# BeagleBone_Blue.net
KiCad netlist of a schematic drawn in EAGLE
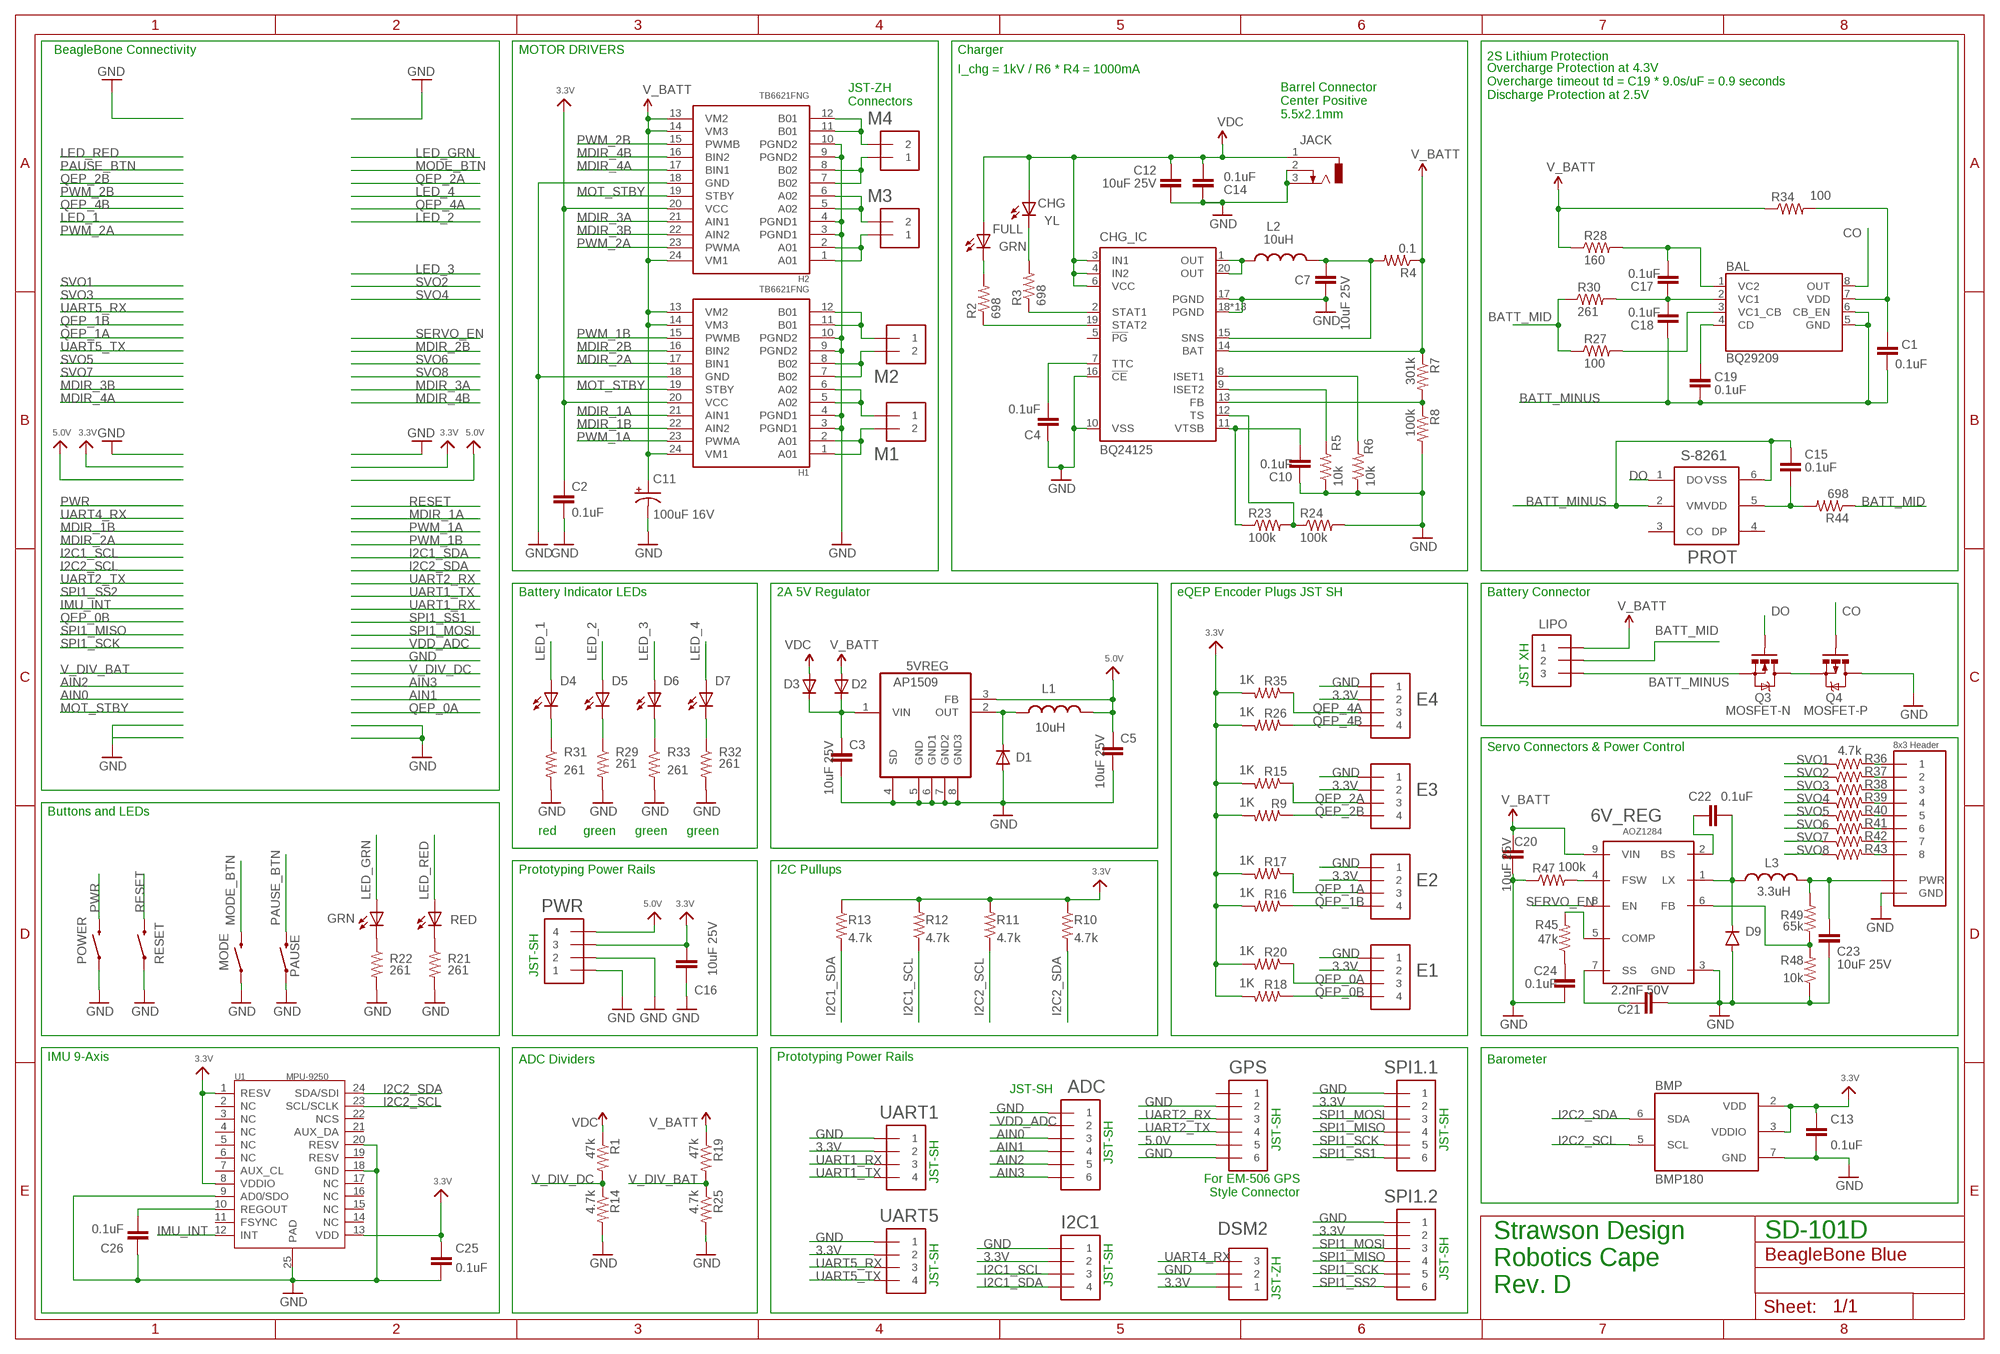
[diagram p0: schematic, sheet 1]

(export (version "E")
  (design (tool "Eeschema 10.0.6"))
  (components
    (comp (ref "5VREG")
      (value "AP1509SOIC-8-TIGHT")
      (footprint "eagle-import:SO08-TIGHT")
      (libsource (lib "eagle-import") (part "AP1509SOIC-8-TIGHT"))
    )
    (comp (ref "6V_REG")
      (value "AOZ1284")
      (footprint "eagle-import:SO08-EXPOSED")
      (libsource (lib "eagle-import") (part "AOZ1284"))
    )
    (comp (ref "ADC")
      (value "JST_SH_6")
      (footprint "eagle-import:JST_SH_6")
      (libsource (lib "eagle-import") (part "JST_SH_6"))
    )
    (comp (ref "BAL")
      (value "BQ29209")
      (footprint "eagle-import:8-SON_3X3MM")
      (libsource (lib "eagle-import") (part "BQ29209"))
    )
    (comp (ref "BMP")
      (value "BMP180")
      (footprint "eagle-import:BMP180")
      (libsource (lib "eagle-import") (part "BMP180"))
    )
    (comp (ref "C1")
      (value "0.1uF")
      (footprint "eagle-import:0402-CAP")
      (libsource (lib "eagle-import") (part "Strawson_Eagle_Lib_CAP0402-CAP"))
    )
    (comp (ref "C2")
      (value "0.1uF")
      (footprint "eagle-import:0402-CAP")
      (libsource (lib "eagle-import") (part "Strawson_Eagle_Lib_CAP0402-CAP"))
    )
    (comp (ref "C3")
      (value "10uF 25V")
      (footprint "eagle-import:0805")
      (libsource (lib "eagle-import") (part "CAP0805"))
    )
    (comp (ref "C4")
      (value "0.1uF")
      (footprint "eagle-import:0402-CAP")
      (libsource (lib "eagle-import") (part "Strawson_Eagle_Lib_CAP0402-CAP"))
    )
    (comp (ref "C5")
      (value "10uF 25V")
      (footprint "eagle-import:0805")
      (libsource (lib "eagle-import") (part "CAP0805"))
    )
    (comp (ref "C7")
      (value "10uF 25V")
      (footprint "eagle-import:0805")
      (libsource (lib "eagle-import") (part "CAP0805"))
    )
    (comp (ref "C10")
      (value "0.1uF")
      (footprint "eagle-import:0402-CAP")
      (libsource (lib "eagle-import") (part "Strawson_Eagle_Lib_CAP0402-CAP"))
    )
    (comp (ref "C11")
      (value "100uF 16V")
      (footprint "eagle-import:PANASONIC_D")
      (libsource (lib "eagle-import") (part "CPOL-USD"))
    )
    (comp (ref "C12")
      (value "10uF 25V")
      (footprint "eagle-import:0805")
      (libsource (lib "eagle-import") (part "CAP0805"))
    )
    (comp (ref "C13")
      (value "0.1uF")
      (footprint "eagle-import:0402-CAP")
      (libsource (lib "eagle-import") (part "Strawson_Eagle_Lib_CAP0402-CAP"))
    )
    (comp (ref "C14")
      (value "0.1uF")
      (footprint "eagle-import:0402-CAP")
      (libsource (lib "eagle-import") (part "Strawson_Eagle_Lib_CAP0402-CAP"))
    )
    (comp (ref "C15")
      (value "0.1uF")
      (footprint "eagle-import:0402-CAP")
      (libsource (lib "eagle-import") (part "Strawson_Eagle_Lib_CAP0402-CAP"))
    )
    (comp (ref "C16")
      (value "10uF 25V")
      (footprint "eagle-import:0805")
      (libsource (lib "eagle-import") (part "CAP0805"))
    )
    (comp (ref "C17")
      (value "0.1uF")
      (footprint "eagle-import:0402-CAP")
      (libsource (lib "eagle-import") (part "Strawson_Eagle_Lib_CAP0402-CAP"))
    )
    (comp (ref "C18")
      (value "0.1uF")
      (footprint "eagle-import:0402-CAP")
      (libsource (lib "eagle-import") (part "Strawson_Eagle_Lib_CAP0402-CAP"))
    )
    (comp (ref "C19")
      (value "0.1uF")
      (footprint "eagle-import:0402-CAP")
      (libsource (lib "eagle-import") (part "Strawson_Eagle_Lib_CAP0402-CAP"))
    )
    (comp (ref "C20")
      (value "10uF 25V")
      (footprint "eagle-import:0805")
      (libsource (lib "eagle-import") (part "CAP0805"))
    )
    (comp (ref "C21")
      (value "2.2nF 50V")
      (footprint "eagle-import:0402-CAP")
      (libsource (lib "eagle-import") (part "Strawson_Eagle_Lib_CAP0402-CAP"))
    )
    (comp (ref "C22")
      (value "0.1uF")
      (footprint "eagle-import:0402-CAP")
      (libsource (lib "eagle-import") (part "Strawson_Eagle_Lib_CAP0402-CAP"))
    )
    (comp (ref "C23")
      (value "10uF 25V")
      (footprint "eagle-import:0805")
      (libsource (lib "eagle-import") (part "CAP0805"))
    )
    (comp (ref "C24")
      (value "0.1uF")
      (footprint "eagle-import:0402-CAP")
      (libsource (lib "eagle-import") (part "Strawson_Eagle_Lib_CAP0402-CAP"))
    )
    (comp (ref "C25")
      (value "0.1uF")
      (footprint "eagle-import:0402-CAP")
      (libsource (lib "eagle-import") (part "Strawson_Eagle_Lib_CAP0402-CAP"))
    )
    (comp (ref "C26")
      (value "0.1uF")
      (footprint "eagle-import:0402-CAP")
      (libsource (lib "eagle-import") (part "Strawson_Eagle_Lib_CAP0402-CAP"))
    )
    (comp (ref "CHG")
      (value "YL")
      (footprint "eagle-import:LED-0603")
      (libsource (lib "eagle-import") (part "LED0603"))
    )
    (comp (ref "CHG_IC")
      (value "BQ24125")
      (footprint "eagle-import:QFN20_3,5X4,5")
      (fields (field (name "MPN") "BQ24125RHLR"))
      (libsource (lib "eagle-import") (part "BQ24125"))
    )
    (comp (ref "D1")
      (value "DIODESOD-123")
      (footprint "eagle-import:SOD-123")
      (libsource (lib "eagle-import") (part "DIODESOD-123"))
    )
    (comp (ref "D2")
      (value "DIODESOD-123")
      (footprint "eagle-import:SOD-123")
      (libsource (lib "eagle-import") (part "DIODESOD-123"))
    )
    (comp (ref "D3")
      (value "DIODESOD-123")
      (footprint "eagle-import:SOD-123")
      (libsource (lib "eagle-import") (part "DIODESOD-123"))
    )
    (comp (ref "D4")
      (value "RED")
      (footprint "eagle-import:LED-0603")
      (libsource (lib "eagle-import") (part "LED0603"))
    )
    (comp (ref "D5")
      (value "GREEN")
      (footprint "eagle-import:LED-0603")
      (libsource (lib "eagle-import") (part "LED0603"))
    )
    (comp (ref "D6")
      (value "GREEN")
      (footprint "eagle-import:LED-0603")
      (libsource (lib "eagle-import") (part "LED0603"))
    )
    (comp (ref "D7")
      (value "GREEN")
      (footprint "eagle-import:LED-0603")
      (libsource (lib "eagle-import") (part "LED0603"))
    )
    (comp (ref "D9")
      (value "DIODEDO214AA")
      (footprint "eagle-import:DO-214AA")
      (libsource (lib "eagle-import") (part "DIODEDO214AA"))
    )
    (comp (ref "DSM2")
      (value "JST_ZH_3")
      (footprint "eagle-import:JST_ZH_3")
      (libsource (lib "eagle-import") (part "JST_ZH_3"))
    )
    (comp (ref "E1")
      (value "JST_SH_4")
      (footprint "eagle-import:JST_SH_4_SMD")
      (libsource (lib "eagle-import") (part "JST_SH_4"))
    )
    (comp (ref "E2")
      (value "JST_SH_4")
      (footprint "eagle-import:JST_SH_4_SMD")
      (libsource (lib "eagle-import") (part "JST_SH_4"))
    )
    (comp (ref "E3")
      (value "JST_SH_4")
      (footprint "eagle-import:JST_SH_4_SMD")
      (libsource (lib "eagle-import") (part "JST_SH_4"))
    )
    (comp (ref "E4")
      (value "JST_SH_4")
      (footprint "eagle-import:JST_SH_4_SMD")
      (libsource (lib "eagle-import") (part "JST_SH_4"))
    )
    (comp (ref "FULL")
      (value "GRN")
      (footprint "eagle-import:LED-0603")
      (libsource (lib "eagle-import") (part "LED0603"))
    )
    (comp (ref "GPS")
      (value "JST_SH_6")
      (footprint "eagle-import:JST_SH_6")
      (libsource (lib "eagle-import") (part "JST_SH_6"))
    )
    (comp (ref "GRN")
      (value "GRN")
      (footprint "eagle-import:LED-0603")
      (libsource (lib "eagle-import") (part "LED0603"))
    )
    (comp (ref "H1")
      (value "TB6621FNG")
      (footprint "eagle-import:SSOP24")
      (libsource (lib "eagle-import") (part "TB6621FNG"))
    )
    (comp (ref "H2")
      (value "TB6621FNG")
      (footprint "eagle-import:SSOP24")
      (libsource (lib "eagle-import") (part "TB6621FNG"))
    )
    (comp (ref "I2C1")
      (value "JST_SH_4")
      (footprint "eagle-import:JST_SH_4_SMD")
      (libsource (lib "eagle-import") (part "JST_SH_4"))
    )
    (comp (ref "JACK")
      (value "5.5x2.1mm")
      (footprint "eagle-import:DCJ0303")
      (libsource (lib "eagle-import") (part "DCJ0303"))
    )
    (comp (ref "L1")
      (value "10uH")
      (footprint "eagle-import:SRN6045")
      (libsource (lib "eagle-import") (part "INDUCTORBOURNS_SRN6045"))
    )
    (comp (ref "L2")
      (value "10uH")
      (footprint "eagle-import:SRN6045")
      (libsource (lib "eagle-import") (part "INDUCTORBOURNS_SRN6045"))
    )
    (comp (ref "L3")
      (value "3.3uH")
      (footprint "eagle-import:8X8MM_INDUCTOR")
      (libsource (lib "eagle-import") (part "INDUCTOR"))
    )
    (comp (ref "LIPO")
      (value "JST_XH_3-PIN")
      (footprint "eagle-import:JST_XH_3-PIN")
      (libsource (lib "eagle-import") (part "JST_XH_3-PIN"))
    )
    (comp (ref "M1")
      (value "JST_ZH_2")
      (footprint "eagle-import:JST_ZH_2")
      (libsource (lib "eagle-import") (part "JST_ZH_2"))
    )
    (comp (ref "M2")
      (value "JST_ZH_2")
      (footprint "eagle-import:JST_ZH_2")
      (libsource (lib "eagle-import") (part "JST_ZH_2"))
    )
    (comp (ref "M3")
      (value "JST_ZH_2")
      (footprint "eagle-import:JST_ZH_2")
      (libsource (lib "eagle-import") (part "JST_ZH_2"))
    )
    (comp (ref "M4")
      (value "JST_ZH_2")
      (footprint "eagle-import:JST_ZH_2")
      (libsource (lib "eagle-import") (part "JST_ZH_2"))
    )
    (comp (ref "MODE")
      (value "SWITCH-MOMENTARY-2-SMD-1101NE")
      (footprint "eagle-import:TACTILE-SWITCH-1101NE")
      (libsource (lib "eagle-import") (part "SWITCH-MOMENTARY-2-SMD-1101NE"))
    )
    (comp (ref "PAUSE")
      (value "SWITCH-MOMENTARY-2-SMD-1101NE")
      (footprint "eagle-import:TACTILE-SWITCH-1101NE")
      (libsource (lib "eagle-import") (part "SWITCH-MOMENTARY-2-SMD-1101NE"))
    )
    (comp (ref "POWER")
      (value "SWITCH-MOMENTARY-2-SMD-1101NE")
      (footprint "eagle-import:TACTILE-SWITCH-1101NE")
      (libsource (lib "eagle-import") (part "SWITCH-MOMENTARY-2-SMD-1101NE"))
    )
    (comp (ref "PROT")
      (value "S-8261")
      (footprint "eagle-import:SOT-236")
      (libsource (lib "eagle-import") (part "S-8261"))
    )
    (comp (ref "PWR")
      (value "JST_SH_4")
      (footprint "eagle-import:JST_SH_4_SMD")
      (libsource (lib "eagle-import") (part "JST_SH_4"))
    )
    (comp (ref "Q3")
      (value "MOSFET-N")
      (footprint "eagle-import:SO08-TIGHT")
      (libsource (lib "eagle-import") (part "MOSFET-NCHANNEL"))
    )
    (comp (ref "Q4")
      (value "MOSFET-P")
      (footprint "eagle-import:SO08-TIGHT")
      (libsource (lib "eagle-import") (part "MOSFET-PCHANNEL"))
    )
    (comp (ref "R1")
      (value "47k")
      (footprint "eagle-import:0402-RES")
      (libsource (lib "eagle-import") (part "RESISTOR0402-RES"))
    )
    (comp (ref "R2")
      (value "698")
      (footprint "eagle-import:0402-RES")
      (libsource (lib "eagle-import") (part "RESISTOR0402-RES"))
    )
    (comp (ref "R3")
      (value "698")
      (footprint "eagle-import:0402-RES")
      (libsource (lib "eagle-import") (part "RESISTOR0402-RES"))
    )
    (comp (ref "R4")
      (value "0.1")
      (footprint "eagle-import:0603-RES")
      (libsource (lib "eagle-import") (part "RESISTOR0603"))
    )
    (comp (ref "R5")
      (value "10k")
      (footprint "eagle-import:0402-RES")
      (libsource (lib "eagle-import") (part "RESISTOR0402-RES"))
    )
    (comp (ref "R6")
      (value "10k")
      (footprint "eagle-import:0402-RES")
      (libsource (lib "eagle-import") (part "RESISTOR0402-RES"))
    )
    (comp (ref "R7")
      (value "301k")
      (footprint "eagle-import:0402-RES")
      (libsource (lib "eagle-import") (part "RESISTOR0402-RES"))
    )
    (comp (ref "R8")
      (value "100k")
      (footprint "eagle-import:0402-RES")
      (libsource (lib "eagle-import") (part "RESISTOR0402-RES"))
    )
    (comp (ref "R9")
      (value "1K")
      (footprint "eagle-import:0402-RES")
      (libsource (lib "eagle-import") (part "RESISTOR0402-RES"))
    )
    (comp (ref "R10")
      (value "4.7k")
      (footprint "eagle-import:0402-RES")
      (libsource (lib "eagle-import") (part "RESISTOR0402-RES"))
    )
    (comp (ref "R11")
      (value "4.7k")
      (footprint "eagle-import:0402-RES")
      (libsource (lib "eagle-import") (part "RESISTOR0402-RES"))
    )
    (comp (ref "R12")
      (value "4.7k")
      (footprint "eagle-import:0402-RES")
      (libsource (lib "eagle-import") (part "RESISTOR0402-RES"))
    )
    (comp (ref "R13")
      (value "4.7k")
      (footprint "eagle-import:0402-RES")
      (libsource (lib "eagle-import") (part "RESISTOR0402-RES"))
    )
    (comp (ref "R14")
      (value "4.7k")
      (footprint "eagle-import:0402-RES")
      (libsource (lib "eagle-import") (part "RESISTOR0402-RES"))
    )
    (comp (ref "R15")
      (value "1K")
      (footprint "eagle-import:0402-RES")
      (libsource (lib "eagle-import") (part "RESISTOR0402-RES"))
    )
    (comp (ref "R16")
      (value "1K")
      (footprint "eagle-import:0402-RES")
      (libsource (lib "eagle-import") (part "RESISTOR0402-RES"))
    )
    (comp (ref "R17")
      (value "1K")
      (footprint "eagle-import:0402-RES")
      (libsource (lib "eagle-import") (part "RESISTOR0402-RES"))
    )
    (comp (ref "R18")
      (value "1K")
      (footprint "eagle-import:0402-RES")
      (libsource (lib "eagle-import") (part "RESISTOR0402-RES"))
    )
    (comp (ref "R19")
      (value "47k")
      (footprint "eagle-import:0402-RES")
      (libsource (lib "eagle-import") (part "RESISTOR0402-RES"))
    )
    (comp (ref "R20")
      (value "1K")
      (footprint "eagle-import:0402-RES")
      (libsource (lib "eagle-import") (part "RESISTOR0402-RES"))
    )
    (comp (ref "R21")
      (value "261")
      (footprint "eagle-import:0402-RES")
      (libsource (lib "eagle-import") (part "RESISTOR0402-RES"))
    )
    (comp (ref "R22")
      (value "261")
      (footprint "eagle-import:0402-RES")
      (libsource (lib "eagle-import") (part "RESISTOR0402-RES"))
    )
    (comp (ref "R23")
      (value "100k")
      (footprint "eagle-import:0402-RES")
      (libsource (lib "eagle-import") (part "RESISTOR0402-RES"))
    )
    (comp (ref "R24")
      (value "100k")
      (footprint "eagle-import:0402-RES")
      (libsource (lib "eagle-import") (part "RESISTOR0402-RES"))
    )
    (comp (ref "R25")
      (value "4.7k")
      (footprint "eagle-import:0402-RES")
      (libsource (lib "eagle-import") (part "RESISTOR0402-RES"))
    )
    (comp (ref "R26")
      (value "1K")
      (footprint "eagle-import:0402-RES")
      (libsource (lib "eagle-import") (part "RESISTOR0402-RES"))
    )
    (comp (ref "R27")
      (value "100")
      (footprint "eagle-import:0402-RES")
      (libsource (lib "eagle-import") (part "RESISTOR0402-RES"))
    )
    (comp (ref "R28")
      (value "160")
      (footprint "eagle-import:0402-RES")
      (libsource (lib "eagle-import") (part "RESISTOR0402-RES"))
    )
    (comp (ref "R29")
      (value "261")
      (footprint "eagle-import:0402-RES")
      (libsource (lib "eagle-import") (part "RESISTOR0402-RES"))
    )
    (comp (ref "R30")
      (value "261")
      (footprint "eagle-import:0402-RES")
      (libsource (lib "eagle-import") (part "RESISTOR0402-RES"))
    )
    (comp (ref "R31")
      (value "261")
      (footprint "eagle-import:0402-RES")
      (libsource (lib "eagle-import") (part "RESISTOR0402-RES"))
    )
    (comp (ref "R32")
      (value "261")
      (footprint "eagle-import:0402-RES")
      (libsource (lib "eagle-import") (part "RESISTOR0402-RES"))
    )
    (comp (ref "R33")
      (value "261")
      (footprint "eagle-import:0402-RES")
      (libsource (lib "eagle-import") (part "RESISTOR0402-RES"))
    )
    (comp (ref "R34")
      (value "100")
      (footprint "eagle-import:0402-RES")
      (libsource (lib "eagle-import") (part "RESISTOR0402-RES"))
    )
    (comp (ref "R35")
      (value "1K")
      (footprint "eagle-import:0402-RES")
      (libsource (lib "eagle-import") (part "RESISTOR0402-RES"))
    )
    (comp (ref "R36")
      (value "4.7k")
      (footprint "eagle-import:0402-RES")
      (libsource (lib "eagle-import") (part "RESISTOR0402-RES"))
    )
    (comp (ref "R37")
      (value "4.7k")
      (footprint "eagle-import:0402-RES")
      (libsource (lib "eagle-import") (part "RESISTOR0402-RES"))
    )
    (comp (ref "R38")
      (value "4.7k")
      (footprint "eagle-import:0402-RES")
      (libsource (lib "eagle-import") (part "RESISTOR0402-RES"))
    )
    (comp (ref "R39")
      (value "4.7k")
      (footprint "eagle-import:0402-RES")
      (libsource (lib "eagle-import") (part "RESISTOR0402-RES"))
    )
    (comp (ref "R40")
      (value "4.7k")
      (footprint "eagle-import:0402-RES")
      (libsource (lib "eagle-import") (part "RESISTOR0402-RES"))
    )
    (comp (ref "R41")
      (value "4.7k")
      (footprint "eagle-import:0402-RES")
      (libsource (lib "eagle-import") (part "RESISTOR0402-RES"))
    )
    (comp (ref "R42")
      (value "4.7k")
      (footprint "eagle-import:0402-RES")
      (libsource (lib "eagle-import") (part "RESISTOR0402-RES"))
    )
    (comp (ref "R43")
      (value "4.7k")
      (footprint "eagle-import:0402-RES")
      (libsource (lib "eagle-import") (part "RESISTOR0402-RES"))
    )
    (comp (ref "R44")
      (value "698")
      (footprint "eagle-import:0402-RES")
      (libsource (lib "eagle-import") (part "RESISTOR0402-RES"))
    )
    (comp (ref "R45")
      (value "47k")
      (footprint "eagle-import:0402-RES")
      (libsource (lib "eagle-import") (part "RESISTOR0402-RES"))
    )
    (comp (ref "R47")
      (value "100k")
      (footprint "eagle-import:0402-RES")
      (libsource (lib "eagle-import") (part "RESISTOR0402-RES"))
    )
    (comp (ref "R48")
      (value "10k")
      (footprint "eagle-import:0402-RES")
      (libsource (lib "eagle-import") (part "RESISTOR0402-RES"))
    )
    (comp (ref "R49")
      (value "65k")
      (footprint "eagle-import:0402-RES")
      (libsource (lib "eagle-import") (part "RESISTOR0402-RES"))
    )
    (comp (ref "RED")
      (value "RED")
      (footprint "eagle-import:LED-0603")
      (libsource (lib "eagle-import") (part "LED0603"))
    )
    (comp (ref "RESET")
      (value "SWITCH-MOMENTARY-2-SMD-1101NE")
      (footprint "eagle-import:TACTILE-SWITCH-1101NE")
      (libsource (lib "eagle-import") (part "SWITCH-MOMENTARY-2-SMD-1101NE"))
    )
    (comp (ref "SPI1.1")
      (value "JST_SH_6")
      (footprint "eagle-import:JST_SH_6")
      (libsource (lib "eagle-import") (part "JST_SH_6"))
    )
    (comp (ref "SPI1.2")
      (value "JST_SH_6")
      (footprint "eagle-import:JST_SH_6")
      (libsource (lib "eagle-import") (part "JST_SH_6"))
    )
    (comp (ref "U$1")
      (value "SERVO_HEADERS_8X")
      (footprint "eagle-import:3X8_0.1__HEADER")
      (libsource (lib "eagle-import") (part "SERVO_HEADERS_8X"))
    )
    (comp (ref "U1")
      (value "MPU-9250")
      (footprint "eagle-import:QFN24G-0.4-3X3MM")
      (libsource (lib "eagle-import") (part "MPU-9250"))
    )
    (comp (ref "UART1")
      (value "JST_SH_4")
      (footprint "eagle-import:JST_SH_4_SMD")
      (libsource (lib "eagle-import") (part "JST_SH_4"))
    )
    (comp (ref "UART5")
      (value "JST_SH_4")
      (footprint "eagle-import:JST_SH_4_SMD")
      (libsource (lib "eagle-import") (part "JST_SH_4"))
    )
  )
  (nets
    (net (code "1") (name "/AIN0") (class "Default")
      (node (ref "ADC") (pin "3") (pinfunction "3_3") (pintype "bidirectional"))
    )
    (net (code "2") (name "/AIN1") (class "Default")
      (node (ref "ADC") (pin "4") (pinfunction "4_4") (pintype "bidirectional"))
    )
    (net (code "3") (name "/AIN2") (class "Default")
      (node (ref "ADC") (pin "5") (pinfunction "5_5") (pintype "bidirectional"))
    )
    (net (code "4") (name "/AIN3") (class "Default")
      (node (ref "ADC") (pin "6") (pinfunction "6_6") (pintype "bidirectional"))
    )
    (net (code "5") (name "/BATT_MID") (class "Default")
      (node (ref "LIPO") (pin "P$2") (pinfunction "2_P$2") (pintype "passive"))
      (node (ref "R27") (pin "1") (pinfunction "1_1") (pintype "passive"))
      (node (ref "R30") (pin "1") (pinfunction "1_1") (pintype "passive"))
      (node (ref "R44") (pin "1") (pinfunction "1_1") (pintype "passive"))
    )
    (net (code "6") (name "/BATT_MINUS") (class "Default")
      (node (ref "BAL") (pin "5") (pinfunction "GND_5") (pintype "bidirectional"))
      (node (ref "BAL") (pin "6") (pinfunction "CB_EN_6") (pintype "bidirectional"))
      (node (ref "C1") (pin "2") (pinfunction "2_2") (pintype "passive"))
      (node (ref "C15") (pin "1") (pinfunction "1_1") (pintype "passive"))
      (node (ref "C18") (pin "1") (pinfunction "1_1") (pintype "passive"))
      (node (ref "C19") (pin "2") (pinfunction "2_2") (pintype "passive"))
      (node (ref "LIPO") (pin "P$3") (pinfunction "3_P$3") (pintype "passive"))
      (node (ref "PROT") (pin "2") (pinfunction "VM_2") (pintype "bidirectional"))
      (node (ref "PROT") (pin "6") (pinfunction "VSS_6") (pintype "bidirectional"))
      (node (ref "Q3") (pin "1") (pinfunction "S_1") (pintype "passive"))
      (node (ref "Q3") (pin "2") (pinfunction "S_2") (pintype "passive"))
      (node (ref "Q3") (pin "3") (pinfunction "S_3") (pintype "passive"))
    )
    (net (code "7") (name "/CO") (class "Default")
      (node (ref "BAL") (pin "8") (pinfunction "OUT_8") (pintype "bidirectional"))
      (node (ref "Q4") (pin "4") (pinfunction "G_4") (pintype "passive"))
    )
    (net (code "8") (name "/DO") (class "Default")
      (node (ref "PROT") (pin "1") (pinfunction "DO_1") (pintype "bidirectional"))
      (node (ref "Q3") (pin "4") (pinfunction "G_4") (pintype "passive"))
    )
    (net (code "9") (name "/I2C1_SCL") (class "Default")
      (node (ref "I2C1") (pin "3") (pinfunction "3_3") (pintype "bidirectional"))
      (node (ref "R12") (pin "1") (pinfunction "1_1") (pintype "passive"))
    )
    (net (code "10") (name "/I2C1_SDA") (class "Default")
      (node (ref "I2C1") (pin "4") (pinfunction "4_4") (pintype "bidirectional"))
      (node (ref "R13") (pin "2") (pinfunction "2_2") (pintype "passive"))
    )
    (net (code "11") (name "/I2C2_SCL") (class "Default")
      (node (ref "BMP") (pin "5") (pinfunction "SCL_5") (pintype "input"))
      (node (ref "R11") (pin "1") (pinfunction "1_1") (pintype "passive"))
      (node (ref "U1") (pin "23") (pinfunction "SCL/SCLK_23") (pintype "bidirectional"))
    )
    (net (code "12") (name "/I2C2_SDA") (class "Default")
      (node (ref "BMP") (pin "6") (pinfunction "SDA_6") (pintype "bidirectional"))
      (node (ref "R10") (pin "2") (pinfunction "2_2") (pintype "passive"))
      (node (ref "U1") (pin "24") (pinfunction "SDA/SDI_24") (pintype "bidirectional"))
    )
    (net (code "13") (name "/IMU_INT") (class "Default")
      (node (ref "U1") (pin "12") (pinfunction "INT_12") (pintype "bidirectional"))
    )
    (net (code "14") (name "/LED_1") (class "Default")
      (node (ref "D4") (pin "A") (pinfunction "A_A") (pintype "passive"))
    )
    (net (code "15") (name "/LED_2") (class "Default")
      (node (ref "D5") (pin "A") (pinfunction "A_A") (pintype "passive"))
    )
    (net (code "16") (name "/LED_3") (class "Default")
      (node (ref "D6") (pin "A") (pinfunction "A_A") (pintype "passive"))
    )
    (net (code "17") (name "/LED_4") (class "Default")
      (node (ref "D7") (pin "A") (pinfunction "A_A") (pintype "passive"))
    )
    (net (code "18") (name "/LED_GRN") (class "Default")
      (node (ref "GRN") (pin "A") (pinfunction "A_A") (pintype "passive"))
    )
    (net (code "19") (name "/LED_RED") (class "Default")
      (node (ref "RED") (pin "A") (pinfunction "A_A") (pintype "passive"))
    )
    (net (code "20") (name "/MDIR_1A") (class "Default")
      (node (ref "H1") (pin "21") (pinfunction "AIN1_21") (pintype "bidirectional"))
    )
    (net (code "21") (name "/MDIR_1B") (class "Default")
      (node (ref "H1") (pin "22") (pinfunction "AIN2_22") (pintype "bidirectional"))
    )
    (net (code "22") (name "/MDIR_2A") (class "Default")
      (node (ref "H1") (pin "17") (pinfunction "BIN1_17") (pintype "bidirectional"))
    )
    (net (code "23") (name "/MDIR_2B") (class "Default")
      (node (ref "H1") (pin "16") (pinfunction "BIN2_16") (pintype "bidirectional"))
    )
    (net (code "24") (name "/MDIR_3A") (class "Default")
      (node (ref "H2") (pin "21") (pinfunction "AIN1_21") (pintype "bidirectional"))
    )
    (net (code "25") (name "/MDIR_3B") (class "Default")
      (node (ref "H2") (pin "22") (pinfunction "AIN2_22") (pintype "bidirectional"))
    )
    (net (code "26") (name "/MDIR_4A") (class "Default")
      (node (ref "H2") (pin "17") (pinfunction "BIN1_17") (pintype "bidirectional"))
    )
    (net (code "27") (name "/MDIR_4B") (class "Default")
      (node (ref "H2") (pin "16") (pinfunction "BIN2_16") (pintype "bidirectional"))
    )
    (net (code "28") (name "/MODE_BTN") (class "Default")
      (node (ref "MODE") (pin "P$2") (pinfunction "2_P$2") (pintype "passive"))
    )
    (net (code "29") (name "/MOT_STBY") (class "Default")
      (node (ref "H1") (pin "19") (pinfunction "STBY_19") (pintype "bidirectional"))
      (node (ref "H2") (pin "19") (pinfunction "STBY_19") (pintype "bidirectional"))
    )
    (net (code "30") (name "/PAUSE_BTN") (class "Default")
      (node (ref "PAUSE") (pin "P$2") (pinfunction "2_P$2") (pintype "passive"))
    )
    (net (code "31") (name "/PWM_1A") (class "Default")
      (node (ref "H1") (pin "23") (pinfunction "PWMA_23") (pintype "bidirectional"))
    )
    (net (code "32") (name "/PWM_1B") (class "Default")
      (node (ref "H1") (pin "15") (pinfunction "PWMB_15") (pintype "bidirectional"))
    )
    (net (code "33") (name "/PWM_2A") (class "Default")
      (node (ref "H2") (pin "23") (pinfunction "PWMA_23") (pintype "bidirectional"))
    )
    (net (code "34") (name "/PWM_2B") (class "Default")
      (node (ref "H2") (pin "15") (pinfunction "PWMB_15") (pintype "bidirectional"))
    )
    (net (code "35") (name "/PWR") (class "Default")
      (node (ref "POWER") (pin "P$2") (pinfunction "2_P$2") (pintype "passive"))
    )
    (net (code "36") (name "/QEP_0A") (class "Default")
      (node (ref "E1") (pin "3") (pinfunction "3_3") (pintype "bidirectional"))
      (node (ref "R20") (pin "1") (pinfunction "1_1") (pintype "passive"))
    )
    (net (code "37") (name "/QEP_0B") (class "Default")
      (node (ref "E1") (pin "4") (pinfunction "4_4") (pintype "bidirectional"))
      (node (ref "R18") (pin "1") (pinfunction "1_1") (pintype "passive"))
    )
    (net (code "38") (name "/QEP_1A") (class "Default")
      (node (ref "E2") (pin "3") (pinfunction "3_3") (pintype "bidirectional"))
      (node (ref "R17") (pin "1") (pinfunction "1_1") (pintype "passive"))
    )
    (net (code "39") (name "/QEP_1B") (class "Default")
      (node (ref "E2") (pin "4") (pinfunction "4_4") (pintype "bidirectional"))
      (node (ref "R16") (pin "1") (pinfunction "1_1") (pintype "passive"))
    )
    (net (code "40") (name "/QEP_2A") (class "Default")
      (node (ref "E3") (pin "3") (pinfunction "3_3") (pintype "bidirectional"))
      (node (ref "R15") (pin "1") (pinfunction "1_1") (pintype "passive"))
    )
    (net (code "41") (name "/QEP_2B") (class "Default")
      (node (ref "E3") (pin "4") (pinfunction "4_4") (pintype "bidirectional"))
      (node (ref "R9") (pin "1") (pinfunction "1_1") (pintype "passive"))
    )
    (net (code "42") (name "/QEP_4A") (class "Default")
      (node (ref "E4") (pin "3") (pinfunction "3_3") (pintype "bidirectional"))
      (node (ref "R35") (pin "1") (pinfunction "1_1") (pintype "passive"))
    )
    (net (code "43") (name "/QEP_4B") (class "Default")
      (node (ref "E4") (pin "4") (pinfunction "4_4") (pintype "bidirectional"))
      (node (ref "R26") (pin "1") (pinfunction "1_1") (pintype "passive"))
    )
    (net (code "44") (name "/RESET") (class "Default")
      (node (ref "RESET") (pin "P$2") (pinfunction "2_P$2") (pintype "passive"))
    )
    (net (code "45") (name "/SERVO_EN") (class "Default")
      (node (ref "6V_REG") (pin "8") (pinfunction "EN_8") (pintype "bidirectional"))
    )
    (net (code "46") (name "/SPI1_MISO") (class "Default")
      (node (ref "SPI1.1") (pin "4") (pinfunction "4_4") (pintype "bidirectional"))
      (node (ref "SPI1.2") (pin "4") (pinfunction "4_4") (pintype "bidirectional"))
    )
    (net (code "47") (name "/SPI1_MOSI") (class "Default")
      (node (ref "SPI1.1") (pin "3") (pinfunction "3_3") (pintype "bidirectional"))
      (node (ref "SPI1.2") (pin "3") (pinfunction "3_3") (pintype "bidirectional"))
    )
    (net (code "48") (name "/SPI1_SCK") (class "Default")
      (node (ref "SPI1.1") (pin "5") (pinfunction "5_5") (pintype "bidirectional"))
      (node (ref "SPI1.2") (pin "5") (pinfunction "5_5") (pintype "bidirectional"))
    )
    (net (code "49") (name "/SPI1_SS1") (class "Default")
      (node (ref "SPI1.1") (pin "6") (pinfunction "6_6") (pintype "bidirectional"))
    )
    (net (code "50") (name "/SPI1_SS2") (class "Default")
      (node (ref "SPI1.2") (pin "6") (pinfunction "6_6") (pintype "bidirectional"))
    )
    (net (code "51") (name "/SVO1") (class "Default")
      (node (ref "R36") (pin "1") (pinfunction "1_1") (pintype "passive"))
    )
    (net (code "52") (name "/SVO2") (class "Default")
      (node (ref "R37") (pin "1") (pinfunction "1_1") (pintype "passive"))
    )
    (net (code "53") (name "/SVO3") (class "Default")
      (node (ref "R38") (pin "1") (pinfunction "1_1") (pintype "passive"))
    )
    (net (code "54") (name "/SVO4") (class "Default")
      (node (ref "R39") (pin "1") (pinfunction "1_1") (pintype "passive"))
    )
    (net (code "55") (name "/SVO5") (class "Default")
      (node (ref "R40") (pin "1") (pinfunction "1_1") (pintype "passive"))
    )
    (net (code "56") (name "/SVO6") (class "Default")
      (node (ref "R41") (pin "1") (pinfunction "1_1") (pintype "passive"))
    )
    (net (code "57") (name "/SVO7") (class "Default")
      (node (ref "R42") (pin "1") (pinfunction "1_1") (pintype "passive"))
    )
    (net (code "58") (name "/SVO8") (class "Default")
      (node (ref "R43") (pin "1") (pinfunction "1_1") (pintype "passive"))
    )
    (net (code "59") (name "/UART1_RX") (class "Default")
      (node (ref "UART1") (pin "3") (pinfunction "3_3") (pintype "bidirectional"))
    )
    (net (code "60") (name "/UART1_TX") (class "Default")
      (node (ref "UART1") (pin "4") (pinfunction "4_4") (pintype "bidirectional"))
    )
    (net (code "61") (name "/UART2_RX") (class "Default")
      (node (ref "GPS") (pin "3") (pinfunction "3_3") (pintype "bidirectional"))
    )
    (net (code "62") (name "/UART2_TX") (class "Default")
      (node (ref "GPS") (pin "4") (pinfunction "4_4") (pintype "bidirectional"))
    )
    (net (code "63") (name "/UART4_RX") (class "Default")
      (node (ref "DSM2") (pin "P$3") (pinfunction "3_P$3") (pintype "bidirectional"))
    )
    (net (code "64") (name "/UART5_RX") (class "Default")
      (node (ref "UART5") (pin "3") (pinfunction "3_3") (pintype "bidirectional"))
    )
    (net (code "65") (name "/UART5_TX") (class "Default")
      (node (ref "UART5") (pin "4") (pinfunction "4_4") (pintype "bidirectional"))
    )
    (net (code "66") (name "/VDD_ADC") (class "Default")
      (node (ref "ADC") (pin "2") (pinfunction "2_2") (pintype "bidirectional"))
    )
    (net (code "67") (name "/V_DIV_BAT") (class "Default")
      (node (ref "R19") (pin "2") (pinfunction "2_2") (pintype "passive"))
      (node (ref "R25") (pin "1") (pinfunction "1_1") (pintype "passive"))
    )
    (net (code "68") (name "/V_DIV_DC") (class "Default")
      (node (ref "R1") (pin "2") (pinfunction "2_2") (pintype "passive"))
      (node (ref "R14") (pin "1") (pinfunction "1_1") (pintype "passive"))
    )
    (net (code "69") (name "3.3V") (class "Default")
      (node (ref "BMP") (pin "2") (pinfunction "VDD_2") (pintype "power_in"))
      (node (ref "BMP") (pin "3") (pinfunction "VDDIO_3") (pintype "power_in"))
      (node (ref "C13") (pin "1") (pinfunction "1_1") (pintype "passive"))
      (node (ref "C16") (pin "1") (pinfunction "1_1") (pintype "passive"))
      (node (ref "C2") (pin "2") (pinfunction "2_2") (pintype "passive"))
      (node (ref "C25") (pin "1") (pinfunction "1_1") (pintype "passive"))
      (node (ref "DSM2") (pin "P$1") (pinfunction "1_P$1") (pintype "bidirectional"))
      (node (ref "E1") (pin "2") (pinfunction "2_2") (pintype "bidirectional"))
      (node (ref "E2") (pin "2") (pinfunction "2_2") (pintype "bidirectional"))
      (node (ref "E3") (pin "2") (pinfunction "2_2") (pintype "bidirectional"))
      (node (ref "E4") (pin "2") (pinfunction "2_2") (pintype "bidirectional"))
      (node (ref "H1") (pin "20") (pinfunction "VCC_20") (pintype "bidirectional"))
      (node (ref "H2") (pin "20") (pinfunction "VCC_20") (pintype "bidirectional"))
      (node (ref "I2C1") (pin "2") (pinfunction "2_2") (pintype "bidirectional"))
      (node (ref "PWR") (pin "3") (pinfunction "3_3") (pintype "bidirectional"))
      (node (ref "R10") (pin "1") (pinfunction "1_1") (pintype "passive"))
      (node (ref "R11") (pin "2") (pinfunction "2_2") (pintype "passive"))
      (node (ref "R12") (pin "2") (pinfunction "2_2") (pintype "passive"))
      (node (ref "R13") (pin "1") (pinfunction "1_1") (pintype "passive"))
      (node (ref "R15") (pin "2") (pinfunction "2_2") (pintype "passive"))
      (node (ref "R16") (pin "2") (pinfunction "2_2") (pintype "passive"))
      (node (ref "R17") (pin "2") (pinfunction "2_2") (pintype "passive"))
      (node (ref "R18") (pin "2") (pinfunction "2_2") (pintype "passive"))
      (node (ref "R20") (pin "2") (pinfunction "2_2") (pintype "passive"))
      (node (ref "R26") (pin "2") (pinfunction "2_2") (pintype "passive"))
      (node (ref "R35") (pin "2") (pinfunction "2_2") (pintype "passive"))
      (node (ref "R9") (pin "2") (pinfunction "2_2") (pintype "passive"))
      (node (ref "SPI1.1") (pin "2") (pinfunction "2_2") (pintype "bidirectional"))
      (node (ref "SPI1.2") (pin "2") (pinfunction "2_2") (pintype "bidirectional"))
      (node (ref "U1") (pin "1") (pinfunction "RESV_1") (pintype "bidirectional"))
      (node (ref "U1") (pin "13") (pinfunction "VDD_13") (pintype "bidirectional"))
      (node (ref "U1") (pin "8") (pinfunction "VDDIO_8") (pintype "bidirectional"))
      (node (ref "UART1") (pin "2") (pinfunction "2_2") (pintype "bidirectional"))
      (node (ref "UART5") (pin "2") (pinfunction "2_2") (pintype "bidirectional"))
    )
    (net (code "70") (name "5.0V") (class "Default")
      (node (ref "5VREG") (pin "3") (pinfunction "FB_3") (pintype "output"))
      (node (ref "C5") (pin "1") (pinfunction "1_1") (pintype "passive"))
      (node (ref "GPS") (pin "5") (pinfunction "5_5") (pintype "bidirectional"))
      (node (ref "L1") (pin "2") (pinfunction "2_2") (pintype "passive"))
      (node (ref "PWR") (pin "4") (pinfunction "4_4") (pintype "bidirectional"))
    )
    (net (code "71") (name "GND") (class "Default")
      (node (ref "5VREG") (pin "4") (pinfunction "SD_4") (pintype "input"))
      (node (ref "5VREG") (pin "5") (pinfunction "GND_5") (pintype "power_in"))
      (node (ref "5VREG") (pin "6") (pinfunction "GND1_6") (pintype "input"))
      (node (ref "5VREG") (pin "7") (pinfunction "GND2_7") (pintype "passive"))
      (node (ref "5VREG") (pin "8") (pinfunction "GND3_8") (pintype "power_in"))
      (node (ref "6V_REG") (pin "3") (pinfunction "GND_3") (pintype "bidirectional"))
      (node (ref "ADC") (pin "1") (pinfunction "1_1") (pintype "bidirectional"))
      (node (ref "BMP") (pin "7") (pinfunction "GND_7") (pintype "power_in"))
      (node (ref "C10") (pin "1") (pinfunction "1_1") (pintype "passive"))
      (node (ref "C11") (pin "-") (pinfunction "-_-") (pintype "passive"))
      (node (ref "C12") (pin "2") (pinfunction "2_2") (pintype "passive"))
      (node (ref "C13") (pin "2") (pinfunction "2_2") (pintype "passive"))
      (node (ref "C14") (pin "1") (pinfunction "1_1") (pintype "passive"))
      (node (ref "C16") (pin "2") (pinfunction "2_2") (pintype "passive"))
      (node (ref "C2") (pin "1") (pinfunction "1_1") (pintype "passive"))
      (node (ref "C20") (pin "1") (pinfunction "1_1") (pintype "passive"))
      (node (ref "C21") (pin "1") (pinfunction "1_1") (pintype "passive"))
      (node (ref "C23") (pin "1") (pinfunction "1_1") (pintype "passive"))
      (node (ref "C24") (pin "1") (pinfunction "1_1") (pintype "passive"))
      (node (ref "C25") (pin "2") (pinfunction "2_2") (pintype "passive"))
      (node (ref "C26") (pin "1") (pinfunction "1_1") (pintype "passive"))
      (node (ref "C3") (pin "2") (pinfunction "2_2") (pintype "passive"))
      (node (ref "C4") (pin "1") (pinfunction "1_1") (pintype "passive"))
      (node (ref "C5") (pin "2") (pinfunction "2_2") (pintype "passive"))
      (node (ref "C7") (pin "2") (pinfunction "2_2") (pintype "passive"))
      (node (ref "CHG_IC") (pin "10") (pinfunction "VSS_10") (pintype "power_in"))
      (node (ref "CHG_IC") (pin "16") (pinfunction "~{CE}_16") (pintype "input"))
      (node (ref "CHG_IC") (pin "17") (pinfunction "PGND_17") (pintype "input"))
      (node (ref "CHG_IC") (pin "18") (pinfunction "PGND_18") (pintype "input"))
      (node (ref "CHG_IC") (pin "EXP") (pinfunction "PGND_EXP") (pintype "input"))
      (node (ref "CHG_IC") (pin "EXP@10") (pinfunction "PGND_EXP@10") (pintype "input"))
      (node (ref "CHG_IC") (pin "EXP@11") (pinfunction "PGND_EXP@11") (pintype "input"))
      (node (ref "CHG_IC") (pin "EXP@12") (pinfunction "PGND_EXP@12") (pintype "input"))
      (node (ref "CHG_IC") (pin "EXP@7") (pinfunction "PGND_EXP@7") (pintype "input"))
      (node (ref "CHG_IC") (pin "EXP@8") (pinfunction "PGND_EXP@8") (pintype "input"))
      (node (ref "CHG_IC") (pin "EXP@9") (pinfunction "PGND_EXP@9") (pintype "input"))
      (node (ref "CHG_IC") (pin "GND@1") (pinfunction "PGND_GND@1") (pintype "input"))
      (node (ref "CHG_IC") (pin "GND@2") (pinfunction "PGND_GND@2") (pintype "input"))
      (node (ref "CHG_IC") (pin "GND@3") (pinfunction "PGND_GND@3") (pintype "input"))
      (node (ref "CHG_IC") (pin "GND@4") (pinfunction "PGND_GND@4") (pintype "input"))
      (node (ref "CHG_IC") (pin "GND@6") (pinfunction "PGND_GND@6") (pintype "input"))
      (node (ref "D1") (pin "A") (pinfunction "A_A") (pintype "passive"))
      (node (ref "D9") (pin "A") (pinfunction "A_A") (pintype "passive"))
      (node (ref "DSM2") (pin "P$2") (pinfunction "2_P$2") (pintype "bidirectional"))
      (node (ref "E1") (pin "1") (pinfunction "1_1") (pintype "bidirectional"))
      (node (ref "E2") (pin "1") (pinfunction "1_1") (pintype "bidirectional"))
      (node (ref "E3") (pin "1") (pinfunction "1_1") (pintype "bidirectional"))
      (node (ref "E4") (pin "1") (pinfunction "1_1") (pintype "bidirectional"))
      (node (ref "GPS") (pin "2") (pinfunction "2_2") (pintype "bidirectional"))
      (node (ref "GPS") (pin "6") (pinfunction "6_6") (pintype "bidirectional"))
      (node (ref "H1") (pin "10") (pinfunction "PGND2_10") (pintype "bidirectional"))
      (node (ref "H1") (pin "18") (pinfunction "GND_18") (pintype "bidirectional"))
      (node (ref "H1") (pin "3") (pinfunction "PGND1_3") (pintype "bidirectional"))
      (node (ref "H1") (pin "4") (pinfunction "PGND1_4") (pintype "bidirectional"))
      (node (ref "H1") (pin "9") (pinfunction "PGND2_9") (pintype "bidirectional"))
      (node (ref "H2") (pin "10") (pinfunction "PGND2_10") (pintype "bidirectional"))
      (node (ref "H2") (pin "18") (pinfunction "GND_18") (pintype "bidirectional"))
      (node (ref "H2") (pin "3") (pinfunction "PGND1_3") (pintype "bidirectional"))
      (node (ref "H2") (pin "4") (pinfunction "PGND1_4") (pintype "bidirectional"))
      (node (ref "H2") (pin "9") (pinfunction "PGND2_9") (pintype "bidirectional"))
      (node (ref "I2C1") (pin "1") (pinfunction "1_1") (pintype "bidirectional"))
      (node (ref "JACK") (pin "2") (pinfunction "2_2") (pintype "passive"))
      (node (ref "JACK") (pin "3") (pinfunction "3_3") (pintype "passive"))
      (node (ref "MODE") (pin "P$1") (pinfunction "1_P$1") (pintype "passive"))
      (node (ref "PAUSE") (pin "P$1") (pinfunction "1_P$1") (pintype "passive"))
      (node (ref "POWER") (pin "P$1") (pinfunction "1_P$1") (pintype "passive"))
      (node (ref "PWR") (pin "1") (pinfunction "1_1") (pintype "bidirectional"))
      (node (ref "PWR") (pin "2") (pinfunction "2_2") (pintype "bidirectional"))
      (node (ref "Q4") (pin "5") (pinfunction "D_5") (pintype "passive"))
      (node (ref "Q4") (pin "6") (pinfunction "D_6") (pintype "passive"))
      (node (ref "Q4") (pin "7") (pinfunction "D_7") (pintype "passive"))
      (node (ref "Q4") (pin "8") (pinfunction "D_8") (pintype "passive"))
      (node (ref "R14") (pin "2") (pinfunction "2_2") (pintype "passive"))
      (node (ref "R21") (pin "2") (pinfunction "2_2") (pintype "passive"))
      (node (ref "R22") (pin "2") (pinfunction "2_2") (pintype "passive"))
      (node (ref "R24") (pin "2") (pinfunction "2_2") (pintype "passive"))
      (node (ref "R25") (pin "2") (pinfunction "2_2") (pintype "passive"))
      (node (ref "R29") (pin "2") (pinfunction "2_2") (pintype "passive"))
      (node (ref "R31") (pin "2") (pinfunction "2_2") (pintype "passive"))
      (node (ref "R32") (pin "2") (pinfunction "2_2") (pintype "passive"))
      (node (ref "R33") (pin "2") (pinfunction "2_2") (pintype "passive"))
      (node (ref "R47") (pin "1") (pinfunction "1_1") (pintype "passive"))
      (node (ref "R48") (pin "1") (pinfunction "1_1") (pintype "passive"))
      (node (ref "R5") (pin "1") (pinfunction "1_1") (pintype "passive"))
      (node (ref "R6") (pin "1") (pinfunction "1_1") (pintype "passive"))
      (node (ref "R8") (pin "2") (pinfunction "2_2") (pintype "passive"))
      (node (ref "RESET") (pin "P$1") (pinfunction "1_P$1") (pintype "passive"))
      (node (ref "SPI1.1") (pin "1") (pinfunction "1_1") (pintype "bidirectional"))
      (node (ref "SPI1.2") (pin "1") (pinfunction "1_1") (pintype "bidirectional"))
      (node (ref "U$1") (pin "P$13") (pinfunction "GND_P$13") (pintype "bidirectional"))
      (node (ref "U$1") (pin "P$14") (pinfunction "GND_P$14") (pintype "bidirectional"))
      (node (ref "U$1") (pin "P$15") (pinfunction "GND_P$15") (pintype "bidirectional"))
      (node (ref "U$1") (pin "P$16") (pinfunction "GND_P$16") (pintype "bidirectional"))
      (node (ref "U$1") (pin "P$17") (pinfunction "GND_P$17") (pintype "bidirectional"))
      (node (ref "U$1") (pin "P$18") (pinfunction "GND_P$18") (pintype "bidirectional"))
      (node (ref "U$1") (pin "P$23") (pinfunction "GND_P$23") (pintype "bidirectional"))
      (node (ref "U$1") (pin "P$24") (pinfunction "GND_P$24") (pintype "bidirectional"))
      (node (ref "U1") (pin "18") (pinfunction "GND_18") (pintype "bidirectional"))
      (node (ref "U1") (pin "20") (pinfunction "RESV_20") (pintype "bidirectional"))
      (node (ref "U1") (pin "25") (pinfunction "PAD_25") (pintype "bidirectional"))
      (node (ref "U1") (pin "9") (pinfunction "AD0/SDO_9") (pintype "bidirectional"))
      (node (ref "UART1") (pin "1") (pinfunction "1_1") (pintype "bidirectional"))
      (node (ref "UART5") (pin "1") (pinfunction "1_1") (pintype "bidirectional"))
    )
    (net (code "72") (name "Net-(5VREG-OUT)") (class "Default")
      (node (ref "5VREG") (pin "2") (pinfunction "OUT_2") (pintype "output"))
      (node (ref "D1") (pin "C") (pinfunction "C_C") (pintype "passive"))
      (node (ref "L1") (pin "1") (pinfunction "1_1") (pintype "passive"))
    )
    (net (code "73") (name "Net-(5VREG-VIN)") (class "Default")
      (node (ref "5VREG") (pin "1") (pinfunction "VIN_1") (pintype "input"))
      (node (ref "C3") (pin "1") (pinfunction "1_1") (pintype "passive"))
      (node (ref "D2") (pin "C") (pinfunction "C_C") (pintype "passive"))
      (node (ref "D3") (pin "C") (pinfunction "C_C") (pintype "passive"))
    )
    (net (code "74") (name "Net-(6V_REG-BS)") (class "Default")
      (node (ref "6V_REG") (pin "2") (pinfunction "BS_2") (pintype "bidirectional"))
      (node (ref "C22") (pin "1") (pinfunction "1_1") (pintype "passive"))
    )
    (net (code "75") (name "Net-(6V_REG-COMP)") (class "Default")
      (node (ref "6V_REG") (pin "5") (pinfunction "COMP_5") (pintype "bidirectional"))
      (node (ref "R45") (pin "2") (pinfunction "2_2") (pintype "passive"))
    )
    (net (code "76") (name "Net-(6V_REG-FB)") (class "Default")
      (node (ref "6V_REG") (pin "6") (pinfunction "FB_6") (pintype "bidirectional"))
      (node (ref "R48") (pin "2") (pinfunction "2_2") (pintype "passive"))
      (node (ref "R49") (pin "1") (pinfunction "1_1") (pintype "passive"))
    )
    (net (code "77") (name "Net-(6V_REG-FSW)") (class "Default")
      (node (ref "6V_REG") (pin "4") (pinfunction "FSW_4") (pintype "bidirectional"))
      (node (ref "R47") (pin "2") (pinfunction "2_2") (pintype "passive"))
    )
    (net (code "78") (name "Net-(6V_REG-LX)") (class "Default")
      (node (ref "6V_REG") (pin "1") (pinfunction "LX_1") (pintype "bidirectional"))
      (node (ref "C22") (pin "2") (pinfunction "2_2") (pintype "passive"))
      (node (ref "D9") (pin "C") (pinfunction "C_C") (pintype "passive"))
      (node (ref "L3") (pin "1") (pinfunction "1_1") (pintype "passive"))
    )
    (net (code "79") (name "Net-(6V_REG-SS)") (class "Default")
      (node (ref "6V_REG") (pin "7") (pinfunction "SS_7") (pintype "bidirectional"))
      (node (ref "C21") (pin "2") (pinfunction "2_2") (pintype "passive"))
    )
    (net (code "80") (name "Net-(BAL-CD)") (class "Default")
      (node (ref "BAL") (pin "4") (pinfunction "CD_4") (pintype "bidirectional"))
      (node (ref "C19") (pin "1") (pinfunction "1_1") (pintype "passive"))
    )
    (net (code "81") (name "Net-(BAL-VC1)") (class "Default")
      (node (ref "BAL") (pin "2") (pinfunction "VC1_2") (pintype "bidirectional"))
      (node (ref "C17") (pin "1") (pinfunction "1_1") (pintype "passive"))
      (node (ref "C18") (pin "2") (pinfunction "2_2") (pintype "passive"))
      (node (ref "R30") (pin "2") (pinfunction "2_2") (pintype "passive"))
    )
    (net (code "82") (name "Net-(BAL-VC1_CB)") (class "Default")
      (node (ref "BAL") (pin "3") (pinfunction "VC1_CB_3") (pintype "bidirectional"))
      (node (ref "R27") (pin "2") (pinfunction "2_2") (pintype "passive"))
    )
    (net (code "83") (name "Net-(BAL-VC2)") (class "Default")
      (node (ref "BAL") (pin "1") (pinfunction "VC2_1") (pintype "bidirectional"))
      (node (ref "C17") (pin "2") (pinfunction "2_2") (pintype "passive"))
      (node (ref "R28") (pin "2") (pinfunction "2_2") (pintype "passive"))
    )
    (net (code "84") (name "Net-(BAL-VDD)") (class "Default")
      (node (ref "BAL") (pin "7") (pinfunction "VDD_7") (pintype "bidirectional"))
      (node (ref "C1") (pin "1") (pinfunction "1_1") (pintype "passive"))
      (node (ref "R34") (pin "2") (pinfunction "2_2") (pintype "passive"))
    )
    (net (code "85") (name "Net-(C23-Pad2)") (class "Default")
      (node (ref "C23") (pin "2") (pinfunction "2_2") (pintype "passive"))
      (node (ref "L3") (pin "2") (pinfunction "2_2") (pintype "passive"))
      (node (ref "R49") (pin "2") (pinfunction "2_2") (pintype "passive"))
      (node (ref "U$1") (pin "P$10") (pinfunction "PWR_P$10") (pintype "bidirectional"))
      (node (ref "U$1") (pin "P$11") (pinfunction "PWR_P$11") (pintype "bidirectional"))
      (node (ref "U$1") (pin "P$12") (pinfunction "PWR_P$12") (pintype "bidirectional"))
      (node (ref "U$1") (pin "P$21") (pinfunction "PWR_P$21") (pintype "bidirectional"))
      (node (ref "U$1") (pin "P$22") (pinfunction "PWR_P$22") (pintype "bidirectional"))
      (node (ref "U$1") (pin "P$7") (pinfunction "PWR_P$7") (pintype "bidirectional"))
      (node (ref "U$1") (pin "P$8") (pinfunction "PWR_P$8") (pintype "bidirectional"))
      (node (ref "U$1") (pin "P$9") (pinfunction "PWR_P$9") (pintype "bidirectional"))
    )
    (net (code "86") (name "Net-(C24-Pad2)") (class "Default")
      (node (ref "C24") (pin "2") (pinfunction "2_2") (pintype "passive"))
      (node (ref "R45") (pin "1") (pinfunction "1_1") (pintype "passive"))
    )
    (net (code "87") (name "Net-(CHG-PadC)") (class "Default")
      (node (ref "CHG") (pin "C") (pinfunction "C_C") (pintype "passive"))
      (node (ref "R3") (pin "2") (pinfunction "2_2") (pintype "passive"))
    )
    (net (code "88") (name "Net-(CHG_IC-FB)") (class "Default")
      (node (ref "CHG_IC") (pin "13") (pinfunction "FB_13") (pintype "input"))
      (node (ref "R7") (pin "2") (pinfunction "2_2") (pintype "passive"))
      (node (ref "R8") (pin "1") (pinfunction "1_1") (pintype "passive"))
    )
    (net (code "89") (name "Net-(CHG_IC-ISET1)") (class "Default")
      (node (ref "CHG_IC") (pin "8") (pinfunction "ISET1_8") (pintype "bidirectional"))
      (node (ref "R6") (pin "2") (pinfunction "2_2") (pintype "passive"))
    )
    (net (code "90") (name "Net-(CHG_IC-ISET2)") (class "Default")
      (node (ref "CHG_IC") (pin "9") (pinfunction "ISET2_9") (pintype "bidirectional"))
      (node (ref "R5") (pin "2") (pinfunction "2_2") (pintype "passive"))
    )
    (net (code "91") (name "Net-(CHG_IC-OUT-Pad1)") (class "Default")
      (node (ref "CHG_IC") (pin "1") (pinfunction "OUT_1") (pintype "output"))
      (node (ref "CHG_IC") (pin "20") (pinfunction "OUT_20") (pintype "input"))
      (node (ref "L2") (pin "1") (pinfunction "1_1") (pintype "passive"))
    )
    (net (code "92") (name "Net-(CHG_IC-SNS)") (class "Default")
      (node (ref "C7") (pin "1") (pinfunction "1_1") (pintype "passive"))
      (node (ref "CHG_IC") (pin "15") (pinfunction "SNS_15") (pintype "input"))
      (node (ref "L2") (pin "2") (pinfunction "2_2") (pintype "passive"))
      (node (ref "R4") (pin "2") (pinfunction "2_2") (pintype "passive"))
    )
    (net (code "93") (name "Net-(CHG_IC-STAT1)") (class "Default")
      (node (ref "CHG_IC") (pin "2") (pinfunction "STAT1_2") (pintype "output"))
      (node (ref "R3") (pin "1") (pinfunction "1_1") (pintype "passive"))
    )
    (net (code "94") (name "Net-(CHG_IC-STAT2)") (class "Default")
      (node (ref "CHG_IC") (pin "19") (pinfunction "STAT2_19") (pintype "output"))
      (node (ref "R2") (pin "1") (pinfunction "1_1") (pintype "passive"))
    )
    (net (code "95") (name "Net-(CHG_IC-TS)") (class "Default")
      (node (ref "CHG_IC") (pin "12") (pinfunction "TS_12") (pintype "input"))
      (node (ref "R23") (pin "2") (pinfunction "2_2") (pintype "passive"))
      (node (ref "R24") (pin "1") (pinfunction "1_1") (pintype "passive"))
    )
    (net (code "96") (name "Net-(CHG_IC-TTC)") (class "Default")
      (node (ref "C4") (pin "2") (pinfunction "2_2") (pintype "passive"))
      (node (ref "CHG_IC") (pin "7") (pinfunction "TTC_7") (pintype "passive"))
    )
    (net (code "97") (name "Net-(CHG_IC-VTSB)") (class "Default")
      (node (ref "C10") (pin "2") (pinfunction "2_2") (pintype "passive"))
      (node (ref "CHG_IC") (pin "11") (pinfunction "VTSB_11") (pintype "output"))
      (node (ref "R23") (pin "1") (pinfunction "1_1") (pintype "passive"))
    )
    (net (code "98") (name "Net-(D4-PadC)") (class "Default")
      (node (ref "D4") (pin "C") (pinfunction "C_C") (pintype "passive"))
      (node (ref "R31") (pin "1") (pinfunction "1_1") (pintype "passive"))
    )
    (net (code "99") (name "Net-(D5-PadC)") (class "Default")
      (node (ref "D5") (pin "C") (pinfunction "C_C") (pintype "passive"))
      (node (ref "R29") (pin "1") (pinfunction "1_1") (pintype "passive"))
    )
    (net (code "100") (name "Net-(D6-PadC)") (class "Default")
      (node (ref "D6") (pin "C") (pinfunction "C_C") (pintype "passive"))
      (node (ref "R33") (pin "1") (pinfunction "1_1") (pintype "passive"))
    )
    (net (code "101") (name "Net-(D7-PadC)") (class "Default")
      (node (ref "D7") (pin "C") (pinfunction "C_C") (pintype "passive"))
      (node (ref "R32") (pin "1") (pinfunction "1_1") (pintype "passive"))
    )
    (net (code "102") (name "Net-(FULL-PadC)") (class "Default")
      (node (ref "FULL") (pin "C") (pinfunction "C_C") (pintype "passive"))
      (node (ref "R2") (pin "2") (pinfunction "2_2") (pintype "passive"))
    )
    (net (code "103") (name "Net-(GRN-PadC)") (class "Default")
      (node (ref "GRN") (pin "C") (pinfunction "C_C") (pintype "passive"))
      (node (ref "R22") (pin "1") (pinfunction "1_1") (pintype "passive"))
    )
    (net (code "104") (name "Net-(M1-1)") (class "Default")
      (node (ref "H1") (pin "5") (pinfunction "A02_5") (pintype "bidirectional"))
      (node (ref "H1") (pin "6") (pinfunction "A02_6") (pintype "bidirectional"))
      (node (ref "M1") (pin "P$1") (pinfunction "1_P$1") (pintype "bidirectional"))
    )
    (net (code "105") (name "Net-(M1-2)") (class "Default")
      (node (ref "H1") (pin "1") (pinfunction "A01_1") (pintype "bidirectional"))
      (node (ref "H1") (pin "2") (pinfunction "A01_2") (pintype "bidirectional"))
      (node (ref "M1") (pin "P$2") (pinfunction "2_P$2") (pintype "bidirectional"))
    )
    (net (code "106") (name "Net-(M2-1)") (class "Default")
      (node (ref "H1") (pin "11") (pinfunction "B01_11") (pintype "bidirectional"))
      (node (ref "H1") (pin "12") (pinfunction "B01_12") (pintype "bidirectional"))
      (node (ref "M2") (pin "P$1") (pinfunction "1_P$1") (pintype "bidirectional"))
    )
    (net (code "107") (name "Net-(M2-2)") (class "Default")
      (node (ref "H1") (pin "7") (pinfunction "B02_7") (pintype "bidirectional"))
      (node (ref "H1") (pin "8") (pinfunction "B02_8") (pintype "bidirectional"))
      (node (ref "M2") (pin "P$2") (pinfunction "2_P$2") (pintype "bidirectional"))
    )
    (net (code "108") (name "Net-(M3-1)") (class "Default")
      (node (ref "H2") (pin "1") (pinfunction "A01_1") (pintype "bidirectional"))
      (node (ref "H2") (pin "2") (pinfunction "A01_2") (pintype "bidirectional"))
      (node (ref "M3") (pin "P$1") (pinfunction "1_P$1") (pintype "bidirectional"))
    )
    (net (code "109") (name "Net-(M3-2)") (class "Default")
      (node (ref "H2") (pin "5") (pinfunction "A02_5") (pintype "bidirectional"))
      (node (ref "H2") (pin "6") (pinfunction "A02_6") (pintype "bidirectional"))
      (node (ref "M3") (pin "P$2") (pinfunction "2_P$2") (pintype "bidirectional"))
    )
    (net (code "110") (name "Net-(M4-1)") (class "Default")
      (node (ref "H2") (pin "7") (pinfunction "B02_7") (pintype "bidirectional"))
      (node (ref "H2") (pin "8") (pinfunction "B02_8") (pintype "bidirectional"))
      (node (ref "M4") (pin "P$1") (pinfunction "1_P$1") (pintype "bidirectional"))
    )
    (net (code "111") (name "Net-(M4-2)") (class "Default")
      (node (ref "H2") (pin "11") (pinfunction "B01_11") (pintype "bidirectional"))
      (node (ref "H2") (pin "12") (pinfunction "B01_12") (pintype "bidirectional"))
      (node (ref "M4") (pin "P$2") (pinfunction "2_P$2") (pintype "bidirectional"))
    )
    (net (code "112") (name "Net-(PROT-VDD)") (class "Default")
      (node (ref "C15") (pin "2") (pinfunction "2_2") (pintype "passive"))
      (node (ref "PROT") (pin "5") (pinfunction "VDD_5") (pintype "bidirectional"))
      (node (ref "R44") (pin "2") (pinfunction "2_2") (pintype "passive"))
    )
    (net (code "113") (name "Net-(Q3-D-Pad5)") (class "Default")
      (node (ref "Q3") (pin "5") (pinfunction "D_5") (pintype "passive"))
      (node (ref "Q3") (pin "6") (pinfunction "D_6") (pintype "passive"))
      (node (ref "Q3") (pin "7") (pinfunction "D_7") (pintype "passive"))
      (node (ref "Q3") (pin "8") (pinfunction "D_8") (pintype "passive"))
      (node (ref "Q4") (pin "1") (pinfunction "S_1") (pintype "passive"))
      (node (ref "Q4") (pin "2") (pinfunction "S_2") (pintype "passive"))
      (node (ref "Q4") (pin "3") (pinfunction "S_3") (pintype "passive"))
    )
    (net (code "114") (name "Net-(R21-Pad1)") (class "Default")
      (node (ref "R21") (pin "1") (pinfunction "1_1") (pintype "passive"))
      (node (ref "RED") (pin "C") (pinfunction "C_C") (pintype "passive"))
    )
    (net (code "115") (name "Net-(U$1-1)") (class "Default")
      (node (ref "R36") (pin "2") (pinfunction "2_2") (pintype "passive"))
      (node (ref "U$1") (pin "P$1") (pinfunction "1_P$1") (pintype "bidirectional"))
    )
    (net (code "116") (name "Net-(U$1-2)") (class "Default")
      (node (ref "R37") (pin "2") (pinfunction "2_2") (pintype "passive"))
      (node (ref "U$1") (pin "P$2") (pinfunction "2_P$2") (pintype "bidirectional"))
    )
    (net (code "117") (name "Net-(U$1-3)") (class "Default")
      (node (ref "R38") (pin "2") (pinfunction "2_2") (pintype "passive"))
      (node (ref "U$1") (pin "P$3") (pinfunction "3_P$3") (pintype "bidirectional"))
    )
    (net (code "118") (name "Net-(U$1-4)") (class "Default")
      (node (ref "R39") (pin "2") (pinfunction "2_2") (pintype "passive"))
      (node (ref "U$1") (pin "P$4") (pinfunction "4_P$4") (pintype "bidirectional"))
    )
    (net (code "119") (name "Net-(U$1-5)") (class "Default")
      (node (ref "R40") (pin "2") (pinfunction "2_2") (pintype "passive"))
      (node (ref "U$1") (pin "P$5") (pinfunction "5_P$5") (pintype "bidirectional"))
    )
    (net (code "120") (name "Net-(U$1-6)") (class "Default")
      (node (ref "R41") (pin "2") (pinfunction "2_2") (pintype "passive"))
      (node (ref "U$1") (pin "P$6") (pinfunction "6_P$6") (pintype "bidirectional"))
    )
    (net (code "121") (name "Net-(U$1-7)") (class "Default")
      (node (ref "R42") (pin "2") (pinfunction "2_2") (pintype "passive"))
      (node (ref "U$1") (pin "P$19") (pinfunction "7_P$19") (pintype "bidirectional"))
    )
    (net (code "122") (name "Net-(U$1-8)") (class "Default")
      (node (ref "R43") (pin "2") (pinfunction "2_2") (pintype "passive"))
      (node (ref "U$1") (pin "P$20") (pinfunction "8_P$20") (pintype "bidirectional"))
    )
    (net (code "123") (name "Net-(U1-REGOUT)") (class "Default")
      (node (ref "C26") (pin "2") (pinfunction "2_2") (pintype "passive"))
      (node (ref "U1") (pin "10") (pinfunction "REGOUT_10") (pintype "bidirectional"))
    )
    (net (code "124") (name "VDC") (class "Default")
      (node (ref "C12") (pin "1") (pinfunction "1_1") (pintype "passive"))
      (node (ref "C14") (pin "2") (pinfunction "2_2") (pintype "passive"))
      (node (ref "CHG") (pin "A") (pinfunction "A_A") (pintype "passive"))
      (node (ref "CHG_IC") (pin "3") (pinfunction "IN1_3") (pintype "input"))
      (node (ref "CHG_IC") (pin "4") (pinfunction "IN2_4") (pintype "input"))
      (node (ref "CHG_IC") (pin "6") (pinfunction "VCC_6") (pintype "input"))
      (node (ref "D3") (pin "A") (pinfunction "A_A") (pintype "passive"))
      (node (ref "FULL") (pin "A") (pinfunction "A_A") (pintype "passive"))
      (node (ref "JACK") (pin "1") (pinfunction "1_1") (pintype "passive"))
      (node (ref "R1") (pin "1") (pinfunction "1_1") (pintype "passive"))
    )
    (net (code "125") (name "V_BATT") (class "Default")
      (node (ref "6V_REG") (pin "9") (pinfunction "VIN_9") (pintype "bidirectional"))
      (node (ref "C11") (pin "+") (pinfunction "+_+") (pintype "passive"))
      (node (ref "C20") (pin "2") (pinfunction "2_2") (pintype "passive"))
      (node (ref "CHG_IC") (pin "14") (pinfunction "BAT_14") (pintype "input"))
      (node (ref "D2") (pin "A") (pinfunction "A_A") (pintype "passive"))
      (node (ref "H1") (pin "13") (pinfunction "VM2_13") (pintype "bidirectional"))
      (node (ref "H1") (pin "14") (pinfunction "VM3_14") (pintype "bidirectional"))
      (node (ref "H1") (pin "24") (pinfunction "VM1_24") (pintype "bidirectional"))
      (node (ref "H2") (pin "13") (pinfunction "VM2_13") (pintype "bidirectional"))
      (node (ref "H2") (pin "14") (pinfunction "VM3_14") (pintype "bidirectional"))
      (node (ref "H2") (pin "24") (pinfunction "VM1_24") (pintype "bidirectional"))
      (node (ref "LIPO") (pin "P$1") (pinfunction "1_P$1") (pintype "passive"))
      (node (ref "R19") (pin "1") (pinfunction "1_1") (pintype "passive"))
      (node (ref "R28") (pin "1") (pinfunction "1_1") (pintype "passive"))
      (node (ref "R34") (pin "1") (pinfunction "1_1") (pintype "passive"))
      (node (ref "R4") (pin "1") (pinfunction "1_1") (pintype "passive"))
      (node (ref "R7") (pin "1") (pinfunction "1_1") (pintype "passive"))
    )
    (net (code "126") (name "unconnected-(CHG_IC-~{PG}-Pad5)") (class "Default")
      (node (ref "CHG_IC") (pin "5") (pinfunction "~{PG}_5") (pintype "output"))
    )
    (net (code "127") (name "unconnected-(GPS-Pad1)") (class "Default")
      (node (ref "GPS") (pin "1") (pinfunction "1_1") (pintype "bidirectional"))
    )
    (net (code "128") (name "unconnected-(PROT-CO-Pad3)") (class "Default")
      (node (ref "PROT") (pin "3") (pinfunction "CO_3") (pintype "bidirectional"))
    )
    (net (code "129") (name "unconnected-(PROT-DP-Pad4)") (class "Default")
      (node (ref "PROT") (pin "4") (pinfunction "DP_4") (pintype "bidirectional"))
    )
    (net (code "130") (name "unconnected-(U1-AUX_CL-Pad7)") (class "Default")
      (node (ref "U1") (pin "7") (pinfunction "AUX_CL_7") (pintype "bidirectional"))
    )
    (net (code "131") (name "unconnected-(U1-AUX_DA-Pad21)") (class "Default")
      (node (ref "U1") (pin "21") (pinfunction "AUX_DA_21") (pintype "bidirectional"))
    )
    (net (code "132") (name "unconnected-(U1-FSYNC-Pad11)") (class "Default")
      (node (ref "U1") (pin "11") (pinfunction "FSYNC_11") (pintype "bidirectional"))
    )
    (net (code "133") (name "unconnected-(U1-NC-Pad2)") (class "Default")
      (node (ref "U1") (pin "2") (pinfunction "NC_2") (pintype "bidirectional"))
    )
    (net (code "134") (name "unconnected-(U1-NC-Pad3)") (class "Default")
      (node (ref "U1") (pin "3") (pinfunction "NC_3") (pintype "bidirectional"))
    )
    (net (code "135") (name "unconnected-(U1-NC-Pad4)") (class "Default")
      (node (ref "U1") (pin "4") (pinfunction "NC_4") (pintype "bidirectional"))
    )
    (net (code "136") (name "unconnected-(U1-NC-Pad5)") (class "Default")
      (node (ref "U1") (pin "5") (pinfunction "NC_5") (pintype "bidirectional"))
    )
    (net (code "137") (name "unconnected-(U1-NC-Pad6)") (class "Default")
      (node (ref "U1") (pin "6") (pinfunction "NC_6") (pintype "bidirectional"))
    )
    (net (code "138") (name "unconnected-(U1-NC-Pad14)") (class "Default")
      (node (ref "U1") (pin "14") (pinfunction "NC_14") (pintype "bidirectional"))
    )
    (net (code "139") (name "unconnected-(U1-NC-Pad15)") (class "Default")
      (node (ref "U1") (pin "15") (pinfunction "NC_15") (pintype "bidirectional"))
    )
    (net (code "140") (name "unconnected-(U1-NC-Pad16)") (class "Default")
      (node (ref "U1") (pin "16") (pinfunction "NC_16") (pintype "bidirectional"))
    )
    (net (code "141") (name "unconnected-(U1-NC-Pad17)") (class "Default")
      (node (ref "U1") (pin "17") (pinfunction "NC_17") (pintype "bidirectional"))
    )
    (net (code "142") (name "unconnected-(U1-NCS-Pad22)") (class "Default")
      (node (ref "U1") (pin "22") (pinfunction "NCS_22") (pintype "bidirectional"))
    )
    (net (code "143") (name "unconnected-(U1-RESV-Pad19)") (class "Default")
      (node (ref "U1") (pin "19") (pinfunction "RESV_19") (pintype "bidirectional"))
    )
  )
)
